# KSZ8795CLX.net
KiCad netlist of a schematic drawn in Altium Designer
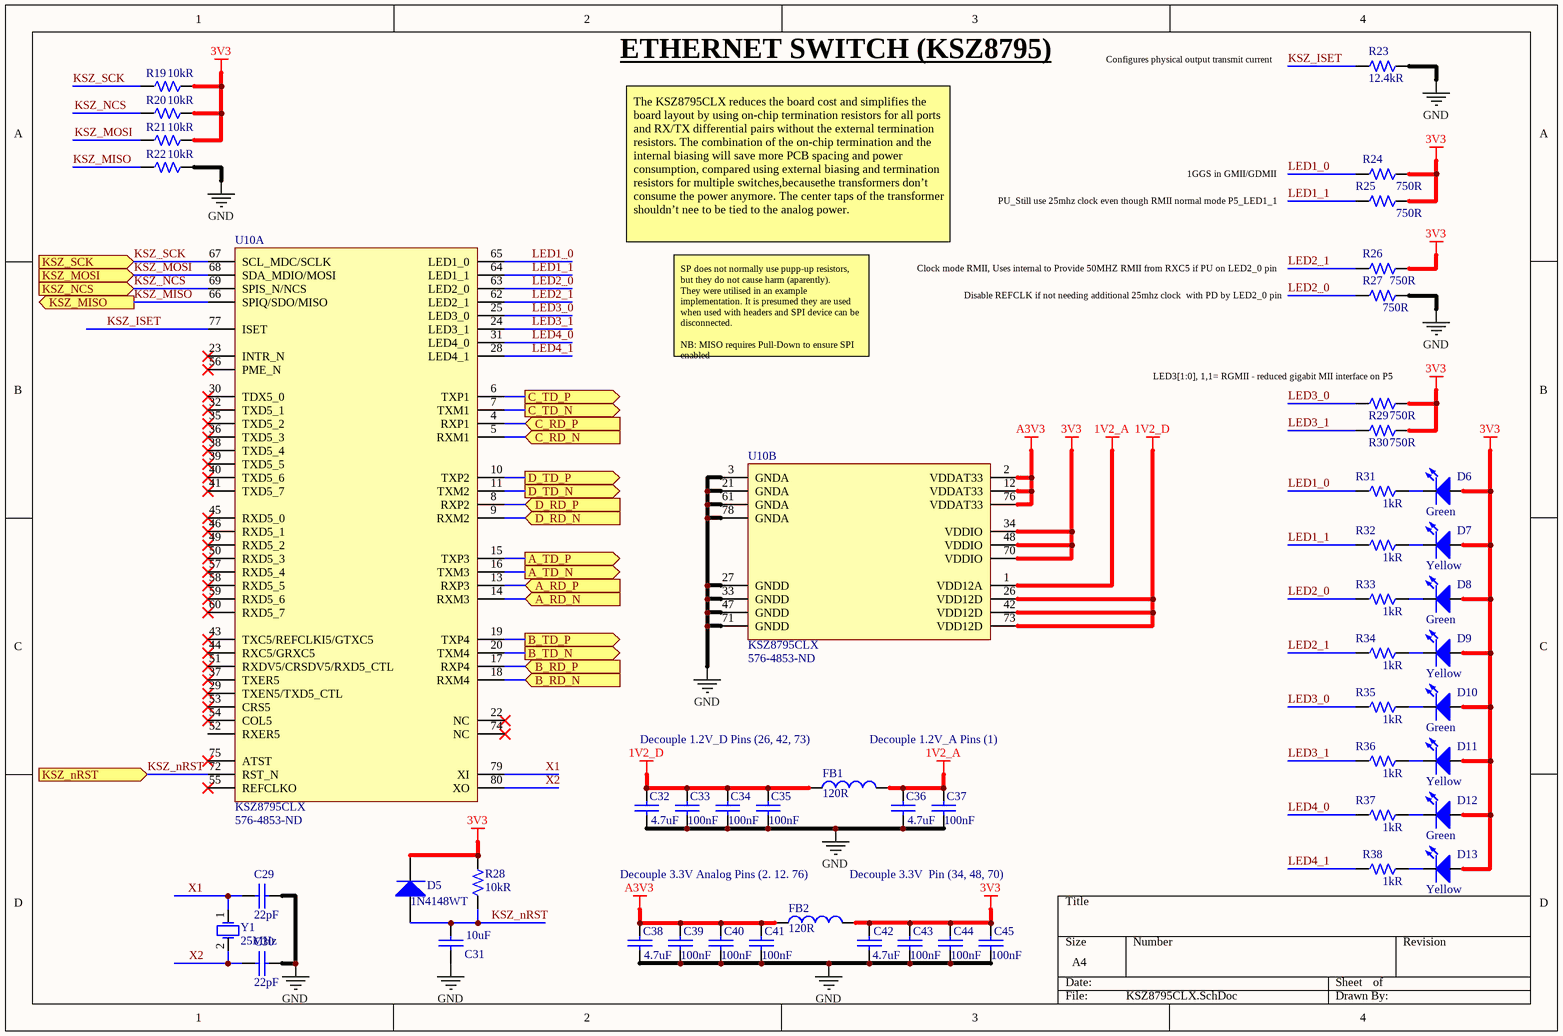
[diagram p0: KSZ8795CLX.SchDoc]

(export (version "E")
  (design (tool "Eeschema 10.0.6"))
  (components
    (comp (ref "C29")
      (value "Capacitor")
      (footprint "CAP0402")
      (fields (field (name "CAPACITANCE") "22pF"))
      (libsource (lib "BPL-ShematicLibrary") (part "Capacitor"))
    )
    (comp (ref "C30")
      (value "Capacitor")
      (footprint "CAP0402")
      (fields (field (name "CAPACITANCE") "22pF"))
      (libsource (lib "BPL-ShematicLibrary") (part "Capacitor"))
    )
    (comp (ref "C31")
      (value "10uF")
      (footprint "CAP0603")
      (description "Capacitor")
      (fields
        (field (name "MANUFACTURER") "Murata")
        (field (name "MANUFACTURER PART NUMBER") "GRM188R61E106MA73J")
      )
      (libsource (lib "BPL-ShematicLibrary") (part "Capacitor"))
    )
    (comp (ref "C32")
      (value "Capacitor")
      (footprint "CAP0402")
      (fields (field (name "CAPACITANCE") "4.7uF"))
      (libsource (lib "BPL-ShematicLibrary") (part "Capacitor"))
    )
    (comp (ref "C33")
      (value "Capacitor")
      (footprint "CAP0402")
      (fields
        (field (name "MANUFACTURER") "TDK")
        (field (name "MANUFACTURER PART NUMBER") "CGA2B3X7R1H104K050BB")
        (field (name "CAPACITANCE") "100nF")
        (field (name "TOLERANCE") "10%")
      )
      (libsource (lib "BPL-ShematicLibrary") (part "Capacitor"))
    )
    (comp (ref "C34")
      (value "Capacitor")
      (footprint "CAP0402")
      (fields
        (field (name "MANUFACTURER") "TDK")
        (field (name "MANUFACTURER PART NUMBER") "CGA2B3X7R1H104K050BB")
        (field (name "CAPACITANCE") "100nF")
        (field (name "TOLERANCE") "10%")
      )
      (libsource (lib "BPL-ShematicLibrary") (part "Capacitor"))
    )
    (comp (ref "C35")
      (value "Capacitor")
      (footprint "CAP0402")
      (fields
        (field (name "MANUFACTURER") "TDK")
        (field (name "MANUFACTURER PART NUMBER") "CGA2B3X7R1H104K050BB")
        (field (name "CAPACITANCE") "100nF")
        (field (name "TOLERANCE") "10%")
      )
      (libsource (lib "BPL-ShematicLibrary") (part "Capacitor"))
    )
    (comp (ref "C36")
      (value "Capacitor")
      (footprint "CAP0402")
      (fields (field (name "CAPACITANCE") "4.7uF"))
      (libsource (lib "BPL-ShematicLibrary") (part "Capacitor"))
    )
    (comp (ref "C37")
      (value "Capacitor")
      (footprint "CAP0402")
      (fields
        (field (name "MANUFACTURER") "TDK")
        (field (name "MANUFACTURER PART NUMBER") "CGA2B3X7R1H104K050BB")
        (field (name "CAPACITANCE") "100nF")
        (field (name "TOLERANCE") "10%")
      )
      (libsource (lib "BPL-ShematicLibrary") (part "Capacitor"))
    )
    (comp (ref "C38")
      (value "Capacitor")
      (footprint "CAP0402")
      (fields (field (name "CAPACITANCE") "4.7uF"))
      (libsource (lib "BPL-ShematicLibrary") (part "Capacitor"))
    )
    (comp (ref "C39")
      (value "Capacitor")
      (footprint "CAP0402")
      (fields
        (field (name "MANUFACTURER") "TDK")
        (field (name "MANUFACTURER PART NUMBER") "CGA2B3X7R1H104K050BB")
        (field (name "CAPACITANCE") "100nF")
        (field (name "TOLERANCE") "10%")
      )
      (libsource (lib "BPL-ShematicLibrary") (part "Capacitor"))
    )
    (comp (ref "C40")
      (value "Capacitor")
      (footprint "CAP0402")
      (fields
        (field (name "MANUFACTURER") "TDK")
        (field (name "MANUFACTURER PART NUMBER") "CGA2B3X7R1H104K050BB")
        (field (name "CAPACITANCE") "100nF")
        (field (name "TOLERANCE") "10%")
      )
      (libsource (lib "BPL-ShematicLibrary") (part "Capacitor"))
    )
    (comp (ref "C41")
      (value "Capacitor")
      (footprint "CAP0402")
      (fields
        (field (name "MANUFACTURER") "TDK")
        (field (name "MANUFACTURER PART NUMBER") "CGA2B3X7R1H104K050BB")
        (field (name "CAPACITANCE") "100nF")
        (field (name "TOLERANCE") "10%")
      )
      (libsource (lib "BPL-ShematicLibrary") (part "Capacitor"))
    )
    (comp (ref "C42")
      (value "Capacitor")
      (footprint "CAP0402")
      (fields (field (name "CAPACITANCE") "4.7uF"))
      (libsource (lib "BPL-ShematicLibrary") (part "Capacitor"))
    )
    (comp (ref "C43")
      (value "Capacitor")
      (footprint "CAP0402")
      (fields
        (field (name "MANUFACTURER") "TDK")
        (field (name "MANUFACTURER PART NUMBER") "CGA2B3X7R1H104K050BB")
        (field (name "CAPACITANCE") "100nF")
        (field (name "TOLERANCE") "10%")
      )
      (libsource (lib "BPL-ShematicLibrary") (part "Capacitor"))
    )
    (comp (ref "C44")
      (value "Capacitor")
      (footprint "CAP0402")
      (fields
        (field (name "MANUFACTURER") "TDK")
        (field (name "MANUFACTURER PART NUMBER") "CGA2B3X7R1H104K050BB")
        (field (name "CAPACITANCE") "100nF")
        (field (name "TOLERANCE") "10%")
      )
      (libsource (lib "BPL-ShematicLibrary") (part "Capacitor"))
    )
    (comp (ref "C45")
      (value "Capacitor")
      (footprint "CAP0402")
      (fields
        (field (name "MANUFACTURER") "TDK")
        (field (name "MANUFACTURER PART NUMBER") "CGA2B3X7R1H104K050BB")
        (field (name "CAPACITANCE") "100nF")
        (field (name "TOLERANCE") "10%")
      )
      (libsource (lib "BPL-ShematicLibrary") (part "Capacitor"))
    )
    (comp (ref "D5")
      (value "Diode")
      (footprint "SOD523")
      (fields (field (name "MANUFACTURER PART NUMBER 1") "1N4148WT"))
      (libsource (lib "BPL-ShematicLibrary") (part "Diode"))
    )
    (comp (ref "D6")
      (value "LED")
      (footprint "LED-0603-GREEN")
      (fields (field (name "COLOR") "Green"))
      (libsource (lib "BPL-ShematicLibrary") (part "LED"))
    )
    (comp (ref "D7")
      (value "LED")
      (footprint "LED-0603-YELLOW")
      (fields (field (name "COLOR") "Yellow"))
      (libsource (lib "BPL-ShematicLibrary") (part "LED"))
    )
    (comp (ref "D8")
      (value "LED")
      (footprint "LED-0603-GREEN")
      (fields (field (name "COLOR") "Green"))
      (libsource (lib "BPL-ShematicLibrary") (part "LED"))
    )
    (comp (ref "D9")
      (value "LED")
      (footprint "LED-0603-YELLOW")
      (fields (field (name "COLOR") "Yellow"))
      (libsource (lib "BPL-ShematicLibrary") (part "LED"))
    )
    (comp (ref "D10")
      (value "LED")
      (footprint "LED-0603-GREEN")
      (fields (field (name "COLOR") "Green"))
      (libsource (lib "BPL-ShematicLibrary") (part "LED"))
    )
    (comp (ref "D11")
      (value "LED")
      (footprint "LED-0603-YELLOW")
      (fields (field (name "COLOR") "Yellow"))
      (libsource (lib "BPL-ShematicLibrary") (part "LED"))
    )
    (comp (ref "D12")
      (value "LED")
      (footprint "LED-0603-GREEN")
      (fields (field (name "COLOR") "Green"))
      (libsource (lib "BPL-ShematicLibrary") (part "LED"))
    )
    (comp (ref "D13")
      (value "LED")
      (footprint "LED-0603-YELLOW")
      (fields (field (name "COLOR") "Yellow"))
      (libsource (lib "BPL-ShematicLibrary") (part "LED"))
    )
    (comp (ref "FB1")
      (value "Ferrite Bead")
      (footprint "RES0402")
      (fields (field (name "TOLERANCE") "25%") (field (name "IMPEDANCE") "120R"))
      (libsource (lib "BPL-ShematicLibrary") (part "Ferrite Bead"))
    )
    (comp (ref "FB2")
      (value "Ferrite Bead")
      (footprint "RES0402")
      (fields (field (name "TOLERANCE") "25%") (field (name "IMPEDANCE") "120R"))
      (libsource (lib "BPL-ShematicLibrary") (part "Ferrite Bead"))
    )
    (comp (ref "R19")
      (value "Resistor")
      (footprint "RES0402")
      (fields (field (name "RESISTANCE") "10kR") (field (name "TOLERANCE") "1%"))
      (libsource (lib "BPL-ShematicLibrary") (part "Resistor"))
    )
    (comp (ref "R20")
      (value "Resistor")
      (footprint "RES0402")
      (fields (field (name "RESISTANCE") "10kR") (field (name "TOLERANCE") "1%"))
      (libsource (lib "BPL-ShematicLibrary") (part "Resistor"))
    )
    (comp (ref "R21")
      (value "Resistor")
      (footprint "RES0402")
      (fields (field (name "RESISTANCE") "10kR") (field (name "TOLERANCE") "1%"))
      (libsource (lib "BPL-ShematicLibrary") (part "Resistor"))
    )
    (comp (ref "R22")
      (value "Resistor")
      (footprint "RES0402")
      (fields (field (name "RESISTANCE") "10kR") (field (name "TOLERANCE") "1%"))
      (libsource (lib "BPL-ShematicLibrary") (part "Resistor"))
    )
    (comp (ref "R23")
      (value "Resistor")
      (footprint "RES0402")
      (fields (field (name "RESISTANCE") "12.4kR") (field (name "TOLERANCE") "0.1%"))
      (libsource (lib "BPL-ShematicLibrary") (part "Resistor"))
    )
    (comp (ref "R24")
      (value "Resistor")
      (footprint "RES0402")
      (fields (field (name "RESISTANCE") "750R") (field (name "TOLERANCE") "1%"))
      (libsource (lib "BPL-ShematicLibrary") (part "Resistor"))
    )
    (comp (ref "R25")
      (value "Resistor")
      (footprint "RES0402")
      (fields (field (name "RESISTANCE") "750R") (field (name "TOLERANCE") "1%"))
      (libsource (lib "BPL-ShematicLibrary") (part "Resistor"))
    )
    (comp (ref "R26")
      (value "Resistor")
      (footprint "RES0402")
      (fields (field (name "RESISTANCE") "750R") (field (name "TOLERANCE") "1%"))
      (libsource (lib "BPL-ShematicLibrary") (part "Resistor"))
    )
    (comp (ref "R27")
      (value "Resistor")
      (footprint "RES0402")
      (fields (field (name "RESISTANCE") "750R") (field (name "TOLERANCE") "1%"))
      (libsource (lib "BPL-ShematicLibrary") (part "Resistor"))
    )
    (comp (ref "R28")
      (value "Resistor")
      (footprint "RES0402")
      (fields (field (name "RESISTANCE") "10kR") (field (name "TOLERANCE") "1%"))
      (libsource (lib "BPL-ShematicLibrary") (part "Resistor"))
    )
    (comp (ref "R29")
      (value "Resistor")
      (footprint "RES0402")
      (fields (field (name "RESISTANCE") "750R") (field (name "TOLERANCE") "1%"))
      (libsource (lib "BPL-ShematicLibrary") (part "Resistor"))
    )
    (comp (ref "R30")
      (value "Resistor")
      (footprint "RES0402")
      (fields (field (name "RESISTANCE") "750R") (field (name "TOLERANCE") "1%"))
      (libsource (lib "BPL-ShematicLibrary") (part "Resistor"))
    )
    (comp (ref "R31")
      (value "Resistor")
      (footprint "RES0402")
      (fields (field (name "TOLERANCE") "5%") (field (name "RESISTANCE") "1kR"))
      (libsource (lib "BPL-ShematicLibrary") (part "Resistor"))
    )
    (comp (ref "R32")
      (value "Resistor")
      (footprint "RES0402")
      (fields (field (name "TOLERANCE") "5%") (field (name "RESISTANCE") "1kR"))
      (libsource (lib "BPL-ShematicLibrary") (part "Resistor"))
    )
    (comp (ref "R33")
      (value "Resistor")
      (footprint "RES0402")
      (fields (field (name "TOLERANCE") "5%") (field (name "RESISTANCE") "1kR"))
      (libsource (lib "BPL-ShematicLibrary") (part "Resistor"))
    )
    (comp (ref "R34")
      (value "Resistor")
      (footprint "RES0402")
      (fields (field (name "TOLERANCE") "5%") (field (name "RESISTANCE") "1kR"))
      (libsource (lib "BPL-ShematicLibrary") (part "Resistor"))
    )
    (comp (ref "R35")
      (value "Resistor")
      (footprint "RES0402")
      (fields (field (name "TOLERANCE") "5%") (field (name "RESISTANCE") "1kR"))
      (libsource (lib "BPL-ShematicLibrary") (part "Resistor"))
    )
    (comp (ref "R36")
      (value "Resistor")
      (footprint "RES0402")
      (fields (field (name "TOLERANCE") "5%") (field (name "RESISTANCE") "1kR"))
      (libsource (lib "BPL-ShematicLibrary") (part "Resistor"))
    )
    (comp (ref "R37")
      (value "Resistor")
      (footprint "RES0402")
      (fields (field (name "TOLERANCE") "5%") (field (name "RESISTANCE") "1kR"))
      (libsource (lib "BPL-ShematicLibrary") (part "Resistor"))
    )
    (comp (ref "R38")
      (value "Resistor")
      (footprint "RES0402")
      (fields (field (name "TOLERANCE") "5%") (field (name "RESISTANCE") "1kR"))
      (libsource (lib "BPL-ShematicLibrary") (part "Resistor"))
    )
    (comp (ref "U10")
      (value "KSZ8795CLX")
      (footprint "KSZ8795CLX")
      (description "5Port   Ethernet Controller 10/100 Base-T/TX PHY MII, RMII Interface 80-LQFP (10x10)")
      (fields (field (name "SUPPLIER PART NUMBER 1") "576-4853-ND"))
      (libsource (lib "BPL-ShematicLibrary") (part "KSZ8795CLX"))
    )
    (comp (ref "Y1")
      (value "Osc")
      (footprint "ABM7 Oscillator")
      (description "Crystal Oscillator")
      (fields (field (name "FREQUENCY") "25MHz") (field (name "TOLERANCE") "20ppm"))
      (libsource (lib "BPL-ShematicLibrary") (part "Crystal Oscillator"))
    )
  )
  (nets
    (net (code "2") (name "/A_RD_N") (class "Default")
      (node (ref "U10") (pin "14") (pinfunction "RXM3_14") (pintype "passive"))
    )
    (net (code "3") (name "/A_RD_P") (class "Default")
      (node (ref "U10") (pin "13") (pinfunction "RXP3_13") (pintype "passive"))
    )
    (net (code "4") (name "/A_TD_N") (class "Default")
      (node (ref "U10") (pin "16") (pinfunction "TXM3_16") (pintype "passive"))
    )
    (net (code "5") (name "/A_TD_P") (class "Default")
      (node (ref "U10") (pin "15") (pinfunction "TXP3_15") (pintype "passive"))
    )
    (net (code "6") (name "/B_RD_N") (class "Default")
      (node (ref "U10") (pin "18") (pinfunction "RXM4_18") (pintype "passive"))
    )
    (net (code "7") (name "/B_RD_P") (class "Default")
      (node (ref "U10") (pin "17") (pinfunction "RXP4_17") (pintype "passive"))
    )
    (net (code "8") (name "/B_TD_N") (class "Default")
      (node (ref "U10") (pin "20") (pinfunction "TXM4_20") (pintype "passive"))
    )
    (net (code "9") (name "/B_TD_P") (class "Default")
      (node (ref "U10") (pin "19") (pinfunction "TXP4_19") (pintype "passive"))
    )
    (net (code "10") (name "/C_RD_N") (class "Default")
      (node (ref "U10") (pin "5") (pinfunction "RXM1_5") (pintype "passive"))
    )
    (net (code "11") (name "/C_RD_P") (class "Default")
      (node (ref "U10") (pin "4") (pinfunction "RXP1_4") (pintype "passive"))
    )
    (net (code "12") (name "/C_TD_N") (class "Default")
      (node (ref "U10") (pin "7") (pinfunction "TXM1_7") (pintype "passive"))
    )
    (net (code "13") (name "/C_TD_P") (class "Default")
      (node (ref "U10") (pin "6") (pinfunction "TXP1_6") (pintype "passive"))
    )
    (net (code "14") (name "/D_RD_N") (class "Default")
      (node (ref "U10") (pin "9") (pinfunction "RXM2_9") (pintype "passive"))
    )
    (net (code "15") (name "/D_RD_P") (class "Default")
      (node (ref "U10") (pin "8") (pinfunction "RXP2_8") (pintype "passive"))
    )
    (net (code "16") (name "/D_TD_N") (class "Default")
      (node (ref "U10") (pin "11") (pinfunction "TXM2_11") (pintype "passive"))
    )
    (net (code "17") (name "/D_TD_P") (class "Default")
      (node (ref "U10") (pin "10") (pinfunction "TXP2_10") (pintype "passive"))
    )
    (net (code "18") (name "/KSZ_ISET") (class "Default")
      (node (ref "R23") (pin "2") (pinfunction "2_2") (pintype "passive"))
      (node (ref "U10") (pin "77") (pinfunction "ISET_77") (pintype "passive"))
    )
    (net (code "19") (name "/KSZ_MISO") (class "Default")
      (node (ref "R22") (pin "1") (pinfunction "1_1") (pintype "passive"))
      (node (ref "U10") (pin "66") (pinfunction "SPIQ/SDO/MISO_66") (pintype "passive"))
    )
    (net (code "20") (name "/KSZ_MOSI") (class "Default")
      (node (ref "R21") (pin "1") (pinfunction "1_1") (pintype "passive"))
      (node (ref "U10") (pin "68") (pinfunction "SDA_MDIO/MOSI_68") (pintype "passive"))
    )
    (net (code "21") (name "/KSZ_NCS") (class "Default")
      (node (ref "R20") (pin "1") (pinfunction "1_1") (pintype "passive"))
      (node (ref "U10") (pin "69") (pinfunction "SPIS_N/NCS_69") (pintype "passive"))
    )
    (net (code "22") (name "/KSZ_SCK") (class "Default")
      (node (ref "R19") (pin "1") (pinfunction "1_1") (pintype "passive"))
      (node (ref "U10") (pin "67") (pinfunction "SCL_MDC/SCLK_67") (pintype "passive"))
    )
    (net (code "23") (name "/KSZ_nRST") (class "Default")
      (node (ref "C31") (pin "1") (pinfunction "1_1") (pintype "passive"))
      (node (ref "D5") (pin "2") (pinfunction "2_2") (pintype "passive"))
      (node (ref "R28") (pin "2") (pinfunction "2_2") (pintype "passive"))
      (node (ref "U10") (pin "72") (pinfunction "RST_N_72") (pintype "passive"))
    )
    (net (code "24") (name "/LED1_0") (class "Default")
      (node (ref "R24") (pin "1") (pinfunction "1_1") (pintype "passive"))
      (node (ref "R31") (pin "1") (pinfunction "1_1") (pintype "passive"))
      (node (ref "U10") (pin "65") (pinfunction "LED1_0_65") (pintype "passive"))
    )
    (net (code "25") (name "/LED1_1") (class "Default")
      (node (ref "R25") (pin "1") (pinfunction "1_1") (pintype "passive"))
      (node (ref "R32") (pin "1") (pinfunction "1_1") (pintype "passive"))
      (node (ref "U10") (pin "64") (pinfunction "LED1_1_64") (pintype "passive"))
    )
    (net (code "26") (name "/LED2_0") (class "Default")
      (node (ref "R27") (pin "1") (pinfunction "1_1") (pintype "passive"))
      (node (ref "R33") (pin "1") (pinfunction "1_1") (pintype "passive"))
      (node (ref "U10") (pin "63") (pinfunction "LED2_0_63") (pintype "passive"))
    )
    (net (code "27") (name "/LED2_1") (class "Default")
      (node (ref "R26") (pin "1") (pinfunction "1_1") (pintype "passive"))
      (node (ref "R34") (pin "1") (pinfunction "1_1") (pintype "passive"))
      (node (ref "U10") (pin "62") (pinfunction "LED2_1_62") (pintype "passive"))
    )
    (net (code "28") (name "/LED3_0") (class "Default")
      (node (ref "R29") (pin "1") (pinfunction "1_1") (pintype "passive"))
      (node (ref "R35") (pin "1") (pinfunction "1_1") (pintype "passive"))
      (node (ref "U10") (pin "25") (pinfunction "LED3_0_25") (pintype "passive"))
    )
    (net (code "29") (name "/LED3_1") (class "Default")
      (node (ref "R30") (pin "1") (pinfunction "1_1") (pintype "passive"))
      (node (ref "R36") (pin "1") (pinfunction "1_1") (pintype "passive"))
      (node (ref "U10") (pin "24") (pinfunction "LED3_1_24") (pintype "passive"))
    )
    (net (code "30") (name "/LED4_0") (class "Default")
      (node (ref "R37") (pin "1") (pinfunction "1_1") (pintype "passive"))
      (node (ref "U10") (pin "31") (pinfunction "LED4_0_31") (pintype "passive"))
    )
    (net (code "31") (name "/LED4_1") (class "Default")
      (node (ref "R38") (pin "1") (pinfunction "1_1") (pintype "passive"))
      (node (ref "U10") (pin "28") (pinfunction "LED4_1_28") (pintype "passive"))
    )
    (net (code "32") (name "/X1") (class "Default")
      (node (ref "C29") (pin "1") (pinfunction "1_1") (pintype "passive"))
      (node (ref "U10") (pin "79") (pinfunction "XI_79") (pintype "passive"))
      (node (ref "Y1") (pin "1") (pinfunction "1_1") (pintype "passive"))
    )
    (net (code "33") (name "/X2") (class "Default")
      (node (ref "C30") (pin "1") (pinfunction "1_1") (pintype "passive"))
      (node (ref "U10") (pin "80") (pinfunction "XO_80") (pintype "passive"))
      (node (ref "Y1") (pin "2") (pinfunction "2_2") (pintype "passive"))
    )
    (net (code "34") (name "1V2_A") (class "Default")
      (node (ref "C36") (pin "1") (pinfunction "1_1") (pintype "passive"))
      (node (ref "C37") (pin "1") (pinfunction "1_1") (pintype "passive"))
      (node (ref "FB1") (pin "2") (pinfunction "2_2") (pintype "passive"))
      (node (ref "U10") (pin "1") (pinfunction "VDD12A_1") (pintype "passive"))
    )
    (net (code "35") (name "1V2_D") (class "Default")
      (node (ref "C32") (pin "1") (pinfunction "1_1") (pintype "passive"))
      (node (ref "C33") (pin "1") (pinfunction "1_1") (pintype "passive"))
      (node (ref "C34") (pin "1") (pinfunction "1_1") (pintype "passive"))
      (node (ref "C35") (pin "1") (pinfunction "1_1") (pintype "passive"))
      (node (ref "FB1") (pin "1") (pinfunction "1_1") (pintype "passive"))
      (node (ref "U10") (pin "26") (pinfunction "VDD12D_26") (pintype "passive"))
      (node (ref "U10") (pin "42") (pinfunction "VDD12D_42") (pintype "passive"))
      (node (ref "U10") (pin "73") (pinfunction "VDD12D_73") (pintype "passive"))
    )
    (net (code "36") (name "3V3") (class "Default")
      (node (ref "C42") (pin "1") (pinfunction "1_1") (pintype "passive"))
      (node (ref "C43") (pin "1") (pinfunction "1_1") (pintype "passive"))
      (node (ref "C44") (pin "1") (pinfunction "1_1") (pintype "passive"))
      (node (ref "C45") (pin "1") (pinfunction "1_1") (pintype "passive"))
      (node (ref "D10") (pin "2") (pinfunction "2_2") (pintype "passive"))
      (node (ref "D11") (pin "2") (pinfunction "2_2") (pintype "passive"))
      (node (ref "D12") (pin "2") (pinfunction "2_2") (pintype "passive"))
      (node (ref "D13") (pin "2") (pinfunction "2_2") (pintype "passive"))
      (node (ref "D5") (pin "1") (pinfunction "1_1") (pintype "passive"))
      (node (ref "D6") (pin "2") (pinfunction "2_2") (pintype "passive"))
      (node (ref "D7") (pin "2") (pinfunction "2_2") (pintype "passive"))
      (node (ref "D8") (pin "2") (pinfunction "2_2") (pintype "passive"))
      (node (ref "D9") (pin "2") (pinfunction "2_2") (pintype "passive"))
      (node (ref "FB2") (pin "2") (pinfunction "2_2") (pintype "passive"))
      (node (ref "R19") (pin "2") (pinfunction "2_2") (pintype "passive"))
      (node (ref "R20") (pin "2") (pinfunction "2_2") (pintype "passive"))
      (node (ref "R21") (pin "2") (pinfunction "2_2") (pintype "passive"))
      (node (ref "R24") (pin "2") (pinfunction "2_2") (pintype "passive"))
      (node (ref "R25") (pin "2") (pinfunction "2_2") (pintype "passive"))
      (node (ref "R26") (pin "2") (pinfunction "2_2") (pintype "passive"))
      (node (ref "R28") (pin "1") (pinfunction "1_1") (pintype "passive"))
      (node (ref "R29") (pin "2") (pinfunction "2_2") (pintype "passive"))
      (node (ref "R30") (pin "2") (pinfunction "2_2") (pintype "passive"))
      (node (ref "U10") (pin "34") (pinfunction "VDDIO_34") (pintype "passive"))
      (node (ref "U10") (pin "48") (pinfunction "VDDIO_48") (pintype "passive"))
      (node (ref "U10") (pin "70") (pinfunction "VDDIO_70") (pintype "passive"))
    )
    (net (code "37") (name "A3V3") (class "Default")
      (node (ref "C38") (pin "1") (pinfunction "1_1") (pintype "passive"))
      (node (ref "C39") (pin "1") (pinfunction "1_1") (pintype "passive"))
      (node (ref "C40") (pin "1") (pinfunction "1_1") (pintype "passive"))
      (node (ref "C41") (pin "1") (pinfunction "1_1") (pintype "passive"))
      (node (ref "FB2") (pin "1") (pinfunction "1_1") (pintype "passive"))
      (node (ref "U10") (pin "12") (pinfunction "VDDAT33_12") (pintype "passive"))
      (node (ref "U10") (pin "2") (pinfunction "VDDAT33_2") (pintype "passive"))
      (node (ref "U10") (pin "76") (pinfunction "VDDAT33_76") (pintype "passive"))
    )
    (net (code "38") (name "GND") (class "Default")
      (node (ref "C29") (pin "2") (pinfunction "2_2") (pintype "passive"))
      (node (ref "C30") (pin "2") (pinfunction "2_2") (pintype "passive"))
      (node (ref "C31") (pin "2") (pinfunction "2_2") (pintype "passive"))
      (node (ref "C32") (pin "2") (pinfunction "2_2") (pintype "passive"))
      (node (ref "C33") (pin "2") (pinfunction "2_2") (pintype "passive"))
      (node (ref "C34") (pin "2") (pinfunction "2_2") (pintype "passive"))
      (node (ref "C35") (pin "2") (pinfunction "2_2") (pintype "passive"))
      (node (ref "C36") (pin "2") (pinfunction "2_2") (pintype "passive"))
      (node (ref "C37") (pin "2") (pinfunction "2_2") (pintype "passive"))
      (node (ref "C38") (pin "2") (pinfunction "2_2") (pintype "passive"))
      (node (ref "C39") (pin "2") (pinfunction "2_2") (pintype "passive"))
      (node (ref "C40") (pin "2") (pinfunction "2_2") (pintype "passive"))
      (node (ref "C41") (pin "2") (pinfunction "2_2") (pintype "passive"))
      (node (ref "C42") (pin "2") (pinfunction "2_2") (pintype "passive"))
      (node (ref "C43") (pin "2") (pinfunction "2_2") (pintype "passive"))
      (node (ref "C44") (pin "2") (pinfunction "2_2") (pintype "passive"))
      (node (ref "C45") (pin "2") (pinfunction "2_2") (pintype "passive"))
      (node (ref "R22") (pin "2") (pinfunction "2_2") (pintype "passive"))
      (node (ref "R23") (pin "1") (pinfunction "1_1") (pintype "passive"))
      (node (ref "R27") (pin "2") (pinfunction "2_2") (pintype "passive"))
      (node (ref "U10") (pin "21") (pinfunction "GNDA_21") (pintype "passive"))
      (node (ref "U10") (pin "27") (pinfunction "GNDD_27") (pintype "passive"))
      (node (ref "U10") (pin "3") (pinfunction "GNDA_3") (pintype "passive"))
      (node (ref "U10") (pin "33") (pinfunction "GNDD_33") (pintype "passive"))
      (node (ref "U10") (pin "47") (pinfunction "GNDD_47") (pintype "passive"))
      (node (ref "U10") (pin "61") (pinfunction "GNDA_61") (pintype "passive"))
      (node (ref "U10") (pin "71") (pinfunction "GNDD_71") (pintype "passive"))
      (node (ref "U10") (pin "78") (pinfunction "GNDA_78") (pintype "passive"))
    )
    (net (code "39") (name "Net-(D6-Pad1)") (class "Default")
      (node (ref "D6") (pin "1") (pinfunction "1_1") (pintype "passive"))
      (node (ref "R31") (pin "2") (pinfunction "2_2") (pintype "passive"))
    )
    (net (code "40") (name "Net-(D7-Pad1)") (class "Default")
      (node (ref "D7") (pin "1") (pinfunction "1_1") (pintype "passive"))
      (node (ref "R32") (pin "2") (pinfunction "2_2") (pintype "passive"))
    )
    (net (code "41") (name "Net-(D8-Pad1)") (class "Default")
      (node (ref "D8") (pin "1") (pinfunction "1_1") (pintype "passive"))
      (node (ref "R33") (pin "2") (pinfunction "2_2") (pintype "passive"))
    )
    (net (code "42") (name "Net-(D9-Pad1)") (class "Default")
      (node (ref "D9") (pin "1") (pinfunction "1_1") (pintype "passive"))
      (node (ref "R34") (pin "2") (pinfunction "2_2") (pintype "passive"))
    )
    (net (code "43") (name "Net-(D10-Pad1)") (class "Default")
      (node (ref "D10") (pin "1") (pinfunction "1_1") (pintype "passive"))
      (node (ref "R35") (pin "2") (pinfunction "2_2") (pintype "passive"))
    )
    (net (code "44") (name "Net-(D11-Pad1)") (class "Default")
      (node (ref "D11") (pin "1") (pinfunction "1_1") (pintype "passive"))
      (node (ref "R36") (pin "2") (pinfunction "2_2") (pintype "passive"))
    )
    (net (code "45") (name "Net-(D12-Pad1)") (class "Default")
      (node (ref "D12") (pin "1") (pinfunction "1_1") (pintype "passive"))
      (node (ref "R37") (pin "2") (pinfunction "2_2") (pintype "passive"))
    )
    (net (code "46") (name "Net-(D13-Pad1)") (class "Default")
      (node (ref "D13") (pin "1") (pinfunction "1_1") (pintype "passive"))
      (node (ref "R38") (pin "2") (pinfunction "2_2") (pintype "passive"))
    )
    (net (code "47") (name "unconnected-(U10A-ATST-Pad75)") (class "Default")
      (node (ref "U10") (pin "75") (pinfunction "ATST_75") (pintype "passive+no_connect"))
    )
    (net (code "48") (name "unconnected-(U10A-COL5-Pad54)") (class "Default")
      (node (ref "U10") (pin "54") (pinfunction "COL5_54") (pintype "passive+no_connect"))
    )
    (net (code "49") (name "unconnected-(U10A-CRS5-Pad53)") (class "Default")
      (node (ref "U10") (pin "53") (pinfunction "CRS5_53") (pintype "passive+no_connect"))
    )
    (net (code "50") (name "unconnected-(U10A-INTR_N-Pad23)") (class "Default")
      (node (ref "U10") (pin "23") (pinfunction "INTR_N_23") (pintype "passive+no_connect"))
    )
    (net (code "51") (name "unconnected-(U10A-NC-Pad22)") (class "Default")
      (node (ref "U10") (pin "22") (pinfunction "NC_22") (pintype "passive+no_connect"))
    )
    (net (code "52") (name "unconnected-(U10A-NC-Pad74)") (class "Default")
      (node (ref "U10") (pin "74") (pinfunction "NC_74") (pintype "passive+no_connect"))
    )
    (net (code "53") (name "unconnected-(U10A-PME_N-Pad56)") (class "Default")
      (node (ref "U10") (pin "56") (pinfunction "PME_N_56") (pintype "passive+no_connect"))
    )
    (net (code "54") (name "unconnected-(U10A-REFCLKO-Pad55)") (class "Default")
      (node (ref "U10") (pin "55") (pinfunction "REFCLKO_55") (pintype "passive+no_connect"))
    )
    (net (code "55") (name "unconnected-(U10A-RXC5{slash}GRXC5-Pad44)") (class "Default")
      (node (ref "U10") (pin "44") (pinfunction "RXC5/GRXC5_44") (pintype "passive+no_connect"))
    )
    (net (code "56") (name "unconnected-(U10A-RXD5_0-Pad45)") (class "Default")
      (node (ref "U10") (pin "45") (pinfunction "RXD5_0_45") (pintype "passive+no_connect"))
    )
    (net (code "57") (name "unconnected-(U10A-RXD5_1-Pad46)") (class "Default")
      (node (ref "U10") (pin "46") (pinfunction "RXD5_1_46") (pintype "passive+no_connect"))
    )
    (net (code "58") (name "unconnected-(U10A-RXD5_2-Pad49)") (class "Default")
      (node (ref "U10") (pin "49") (pinfunction "RXD5_2_49") (pintype "passive+no_connect"))
    )
    (net (code "59") (name "unconnected-(U10A-RXD5_3-Pad50)") (class "Default")
      (node (ref "U10") (pin "50") (pinfunction "RXD5_3_50") (pintype "passive+no_connect"))
    )
    (net (code "60") (name "unconnected-(U10A-RXD5_4-Pad57)") (class "Default")
      (node (ref "U10") (pin "57") (pinfunction "RXD5_4_57") (pintype "passive+no_connect"))
    )
    (net (code "61") (name "unconnected-(U10A-RXD5_5-Pad58)") (class "Default")
      (node (ref "U10") (pin "58") (pinfunction "RXD5_5_58") (pintype "passive+no_connect"))
    )
    (net (code "62") (name "unconnected-(U10A-RXD5_6-Pad59)") (class "Default")
      (node (ref "U10") (pin "59") (pinfunction "RXD5_6_59") (pintype "passive+no_connect"))
    )
    (net (code "63") (name "unconnected-(U10A-RXD5_7-Pad60)") (class "Default")
      (node (ref "U10") (pin "60") (pinfunction "RXD5_7_60") (pintype "passive+no_connect"))
    )
    (net (code "64") (name "unconnected-(U10A-RXDV5{slash}CRSDV5{slash}RXD5_CTL-Pad51)") (class "Default")
      (node (ref "U10") (pin "51") (pinfunction "RXDV5/CRSDV5/RXD5_CTL_51") (pintype "passive+no_connect"))
    )
    (net (code "65") (name "unconnected-(U10A-RXER5-Pad52)") (class "Default")
      (node (ref "U10") (pin "52") (pinfunction "RXER5_52") (pintype "passive"))
    )
    (net (code "66") (name "unconnected-(U10A-TDX5_0-Pad30)") (class "Default")
      (node (ref "U10") (pin "30") (pinfunction "TDX5_0_30") (pintype "passive+no_connect"))
    )
    (net (code "67") (name "unconnected-(U10A-TXC5{slash}REFCLKI5{slash}GTXC5-Pad43)") (class "Default")
      (node (ref "U10") (pin "43") (pinfunction "TXC5/REFCLKI5/GTXC5_43") (pintype "passive+no_connect"))
    )
    (net (code "68") (name "unconnected-(U10A-TXD5_1-Pad32)") (class "Default")
      (node (ref "U10") (pin "32") (pinfunction "TXD5_1_32") (pintype "passive+no_connect"))
    )
    (net (code "69") (name "unconnected-(U10A-TXD5_2-Pad35)") (class "Default")
      (node (ref "U10") (pin "35") (pinfunction "TXD5_2_35") (pintype "passive+no_connect"))
    )
    (net (code "70") (name "unconnected-(U10A-TXD5_3-Pad36)") (class "Default")
      (node (ref "U10") (pin "36") (pinfunction "TXD5_3_36") (pintype "passive+no_connect"))
    )
    (net (code "71") (name "unconnected-(U10A-TXD5_4-Pad38)") (class "Default")
      (node (ref "U10") (pin "38") (pinfunction "TXD5_4_38") (pintype "passive+no_connect"))
    )
    (net (code "72") (name "unconnected-(U10A-TXD5_5-Pad39)") (class "Default")
      (node (ref "U10") (pin "39") (pinfunction "TXD5_5_39") (pintype "passive+no_connect"))
    )
    (net (code "73") (name "unconnected-(U10A-TXD5_6-Pad40)") (class "Default")
      (node (ref "U10") (pin "40") (pinfunction "TXD5_6_40") (pintype "passive+no_connect"))
    )
    (net (code "74") (name "unconnected-(U10A-TXD5_7-Pad41)") (class "Default")
      (node (ref "U10") (pin "41") (pinfunction "TXD5_7_41") (pintype "passive+no_connect"))
    )
    (net (code "75") (name "unconnected-(U10A-TXEN5{slash}TXD5_CTL-Pad29)") (class "Default")
      (node (ref "U10") (pin "29") (pinfunction "TXEN5/TXD5_CTL_29") (pintype "passive+no_connect"))
    )
    (net (code "76") (name "unconnected-(U10A-TXER5-Pad37)") (class "Default")
      (node (ref "U10") (pin "37") (pinfunction "TXER5_37") (pintype "passive+no_connect"))
    )
  )
)
